# twip-mb2.net
KiCad netlist of a schematic drawn in EAGLE
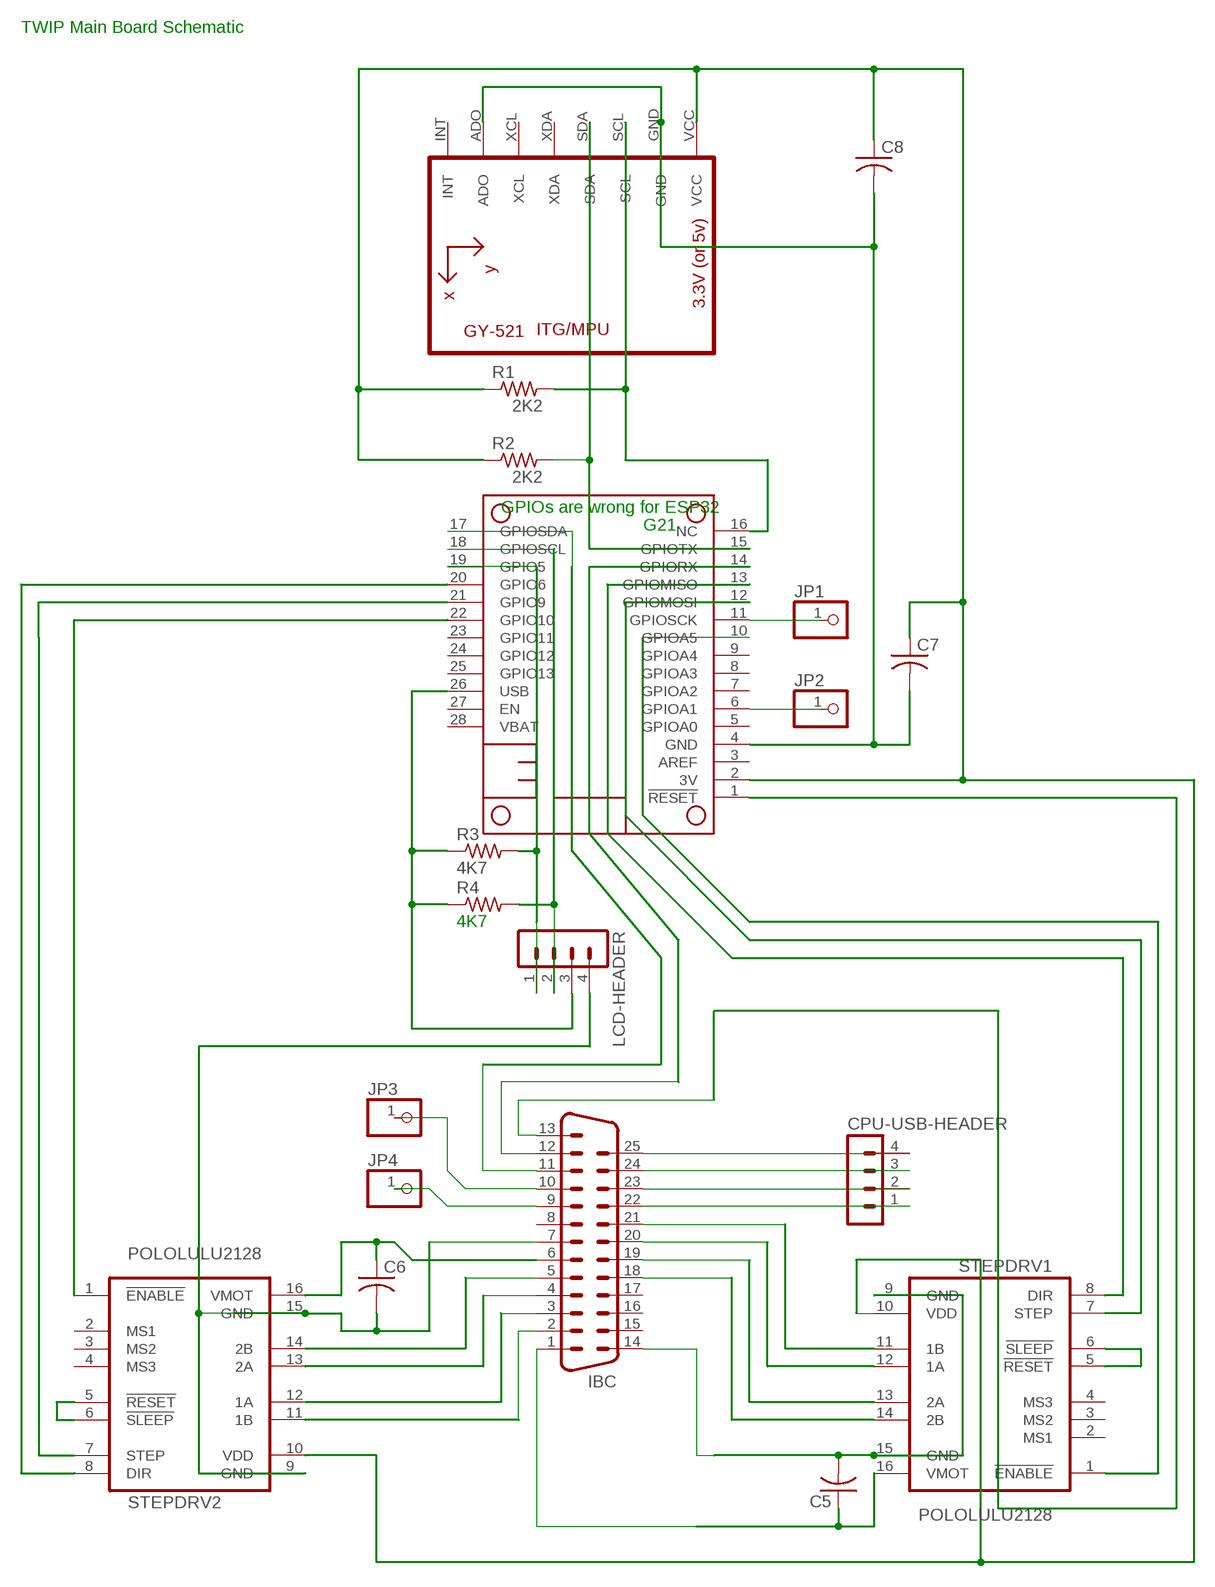
[diagram p0: schematic, sheet 1]

(export (version "E")
  (design (tool "Eeschema 10.0.6"))
  (components
    (comp (ref "C5")
      (value "C-US050-024X044")
      (footprint "eagle-import:C050-024X044")
      (libsource (lib "eagle-import") (part "C-US050-024X044"))
    )
    (comp (ref "C6")
      (value "C-US050-024X044")
      (footprint "eagle-import:C050-024X044")
      (libsource (lib "eagle-import") (part "C-US050-024X044"))
    )
    (comp (ref "C7")
      (value "C-US050-024X044")
      (footprint "eagle-import:C050-024X044")
      (libsource (lib "eagle-import") (part "C-US050-024X044"))
    )
    (comp (ref "C8")
      (value "C-US050-024X044")
      (footprint "eagle-import:C050-024X044")
      (libsource (lib "eagle-import") (part "C-US050-024X044"))
    )
    (comp (ref "CPU-USB-HEADER")
      (value "MA04-1")
      (footprint "eagle-import:MA04-1")
      (libsource (lib "eagle-import") (part "MA04-1"))
    )
    (comp (ref "IBC")
      (value "M25VP")
      (footprint "eagle-import:M25VP")
      (libsource (lib "eagle-import") (part "M25VP"))
    )
    (comp (ref "JP1")
      (value "PINHD-1X1")
      (footprint "eagle-import:1X01")
      (libsource (lib "eagle-import") (part "PINHD-1X1"))
    )
    (comp (ref "JP2")
      (value "PINHD-1X1")
      (footprint "eagle-import:1X01")
      (libsource (lib "eagle-import") (part "PINHD-1X1"))
    )
    (comp (ref "JP3")
      (value "PINHD-1X1")
      (footprint "eagle-import:1X01")
      (libsource (lib "eagle-import") (part "PINHD-1X1"))
    )
    (comp (ref "JP4")
      (value "PINHD-1X1")
      (footprint "eagle-import:1X01")
      (libsource (lib "eagle-import") (part "PINHD-1X1"))
    )
    (comp (ref "LCD-HEADER")
      (value "MA04-1")
      (footprint "eagle-import:MA04-1")
      (libsource (lib "eagle-import") (part "MA04-1"))
    )
    (comp (ref "MS2")
      (value "FEATHERWING_NOHOLES")
      (footprint "eagle-import:FEATHERWING_NOHOLES")
      (libsource (lib "eagle-import") (part "FEATHERWING_NOHOLES"))
    )
    (comp (ref "R1")
      (value "2K2")
      (footprint "eagle-import:0309_12")
      (libsource (lib "eagle-import") (part "R-US_0309/12"))
    )
    (comp (ref "R2")
      (value "2K2")
      (footprint "eagle-import:0309_12")
      (libsource (lib "eagle-import") (part "R-US_0309/12"))
    )
    (comp (ref "R3")
      (value "4K7")
      (footprint "eagle-import:0309_12")
      (libsource (lib "eagle-import") (part "R-US_0309/12"))
    )
    (comp (ref "R4")
      (value "4K7")
      (footprint "eagle-import:0309_12")
      (libsource (lib "eagle-import") (part "R-US_0309/12"))
    )
    (comp (ref "STEPDRV1")
      (value "POLOLULU2128")
      (footprint "eagle-import:POLOLULU2128")
      (libsource (lib "eagle-import") (part "POLOLULU2128"))
    )
    (comp (ref "STEPDRV2")
      (value "POLOLULU2128")
      (footprint "eagle-import:POLOLULU2128")
      (libsource (lib "eagle-import") (part "POLOLULU2128"))
    )
    (comp (ref "U1")
      (value "GY-521MPU6050")
      (footprint "eagle-import:GY-521")
      (libsource (lib "eagle-import") (part "GY-521MPU6050"))
    )
  )
  (nets
    (net (code "1") (name "/VBAT") (class "Default")
      (node (ref "MS2") (pin "28") (pinfunction "VBAT_28") (pintype "power_in"))
    )
    (net (code "2") (name "Net-(C5-Pad2)") (class "Default")
      (node (ref "C5") (pin "2") (pinfunction "2_2") (pintype "passive"))
      (node (ref "IBC") (pin "14") (pinfunction "14_14") (pintype "passive"))
      (node (ref "STEPDRV1") (pin "15") (pinfunction "GND_15") (pintype "power_in"))
      (node (ref "STEPDRV1") (pin "9") (pinfunction "GND_9") (pintype "power_in"))
    )
    (net (code "3") (name "Net-(C6-Pad2)") (class "Default")
      (node (ref "C6") (pin "2") (pinfunction "2_2") (pintype "passive"))
      (node (ref "IBC") (pin "7") (pinfunction "7_7") (pintype "passive"))
      (node (ref "LCD-HEADER") (pin "4") (pinfunction "4_4") (pintype "passive"))
      (node (ref "STEPDRV2") (pin "15") (pinfunction "GND_15") (pintype "power_in"))
      (node (ref "STEPDRV2") (pin "9") (pinfunction "GND_9") (pintype "power_in"))
    )
    (net (code "4") (name "Net-(CPU-USB-HEADER-Pad1)") (class "Default")
      (node (ref "CPU-USB-HEADER") (pin "1") (pinfunction "1_1") (pintype "passive"))
      (node (ref "IBC") (pin "22") (pinfunction "22_22") (pintype "passive"))
    )
    (net (code "5") (name "Net-(CPU-USB-HEADER-Pad2)") (class "Default")
      (node (ref "CPU-USB-HEADER") (pin "2") (pinfunction "2_2") (pintype "passive"))
      (node (ref "IBC") (pin "23") (pinfunction "23_23") (pintype "passive"))
    )
    (net (code "6") (name "Net-(CPU-USB-HEADER-Pad3)") (class "Default")
      (node (ref "CPU-USB-HEADER") (pin "3") (pinfunction "3_3") (pintype "passive"))
      (node (ref "IBC") (pin "24") (pinfunction "24_24") (pintype "passive"))
    )
    (net (code "7") (name "Net-(CPU-USB-HEADER-Pad4)") (class "Default")
      (node (ref "CPU-USB-HEADER") (pin "4") (pinfunction "4_4") (pintype "passive"))
      (node (ref "IBC") (pin "25") (pinfunction "25_25") (pintype "passive"))
    )
    (net (code "8") (name "Net-(IBC-Pad9)") (class "Default")
      (node (ref "IBC") (pin "9") (pinfunction "9_9") (pintype "passive"))
      (node (ref "JP4") (pin "1") (pinfunction "1_1") (pintype "passive"))
    )
    (net (code "9") (name "Net-(IBC-Pad10)") (class "Default")
      (node (ref "IBC") (pin "10") (pinfunction "10_10") (pintype "passive"))
      (node (ref "JP3") (pin "1") (pinfunction "1_1") (pintype "passive"))
    )
    (net (code "10") (name "Net-(MS2-3V)") (class "Default")
      (node (ref "C7") (pin "1") (pinfunction "1_1") (pintype "passive"))
      (node (ref "C8") (pin "1") (pinfunction "1_1") (pintype "passive"))
      (node (ref "MS2") (pin "2") (pinfunction "3V_2") (pintype "power_in"))
      (node (ref "R1") (pin "1") (pinfunction "1_1") (pintype "passive"))
      (node (ref "R2") (pin "1") (pinfunction "1_1") (pintype "passive"))
      (node (ref "STEPDRV1") (pin "10") (pinfunction "VDD_10") (pintype "power_in"))
      (node (ref "STEPDRV2") (pin "10") (pinfunction "VDD_10") (pintype "power_in"))
      (node (ref "U1") (pin "VCC") (pinfunction "VCC_VCC") (pintype "bidirectional"))
    )
    (net (code "11") (name "Net-(MS2-GND)") (class "Default")
      (node (ref "C7") (pin "2") (pinfunction "2_2") (pintype "passive"))
      (node (ref "C8") (pin "2") (pinfunction "2_2") (pintype "passive"))
      (node (ref "MS2") (pin "4") (pinfunction "GND_4") (pintype "power_in"))
      (node (ref "U1") (pin "ADO") (pinfunction "ADO_ADO") (pintype "bidirectional"))
      (node (ref "U1") (pin "GND") (pinfunction "GND_GND") (pintype "bidirectional"))
    )
    (net (code "12") (name "Net-(MS2-GPIO5)") (class "Default")
      (node (ref "LCD-HEADER") (pin "1") (pinfunction "1_1") (pintype "passive"))
      (node (ref "MS2") (pin "19") (pinfunction "GPIO5_19") (pintype "bidirectional"))
      (node (ref "R3") (pin "2") (pinfunction "2_2") (pintype "passive"))
    )
    (net (code "13") (name "Net-(MS2-GPIO6)") (class "Default")
      (node (ref "MS2") (pin "20") (pinfunction "GPIO6_20") (pintype "bidirectional"))
      (node (ref "STEPDRV2") (pin "8") (pinfunction "DIR_8") (pintype "input"))
    )
    (net (code "14") (name "Net-(MS2-GPIO9)") (class "Default")
      (node (ref "MS2") (pin "21") (pinfunction "GPIO9_21") (pintype "bidirectional"))
      (node (ref "STEPDRV2") (pin "7") (pinfunction "STEP_7") (pintype "input"))
    )
    (net (code "15") (name "Net-(MS2-GPIO10)") (class "Default")
      (node (ref "MS2") (pin "22") (pinfunction "GPIO10_22") (pintype "bidirectional"))
      (node (ref "STEPDRV2") (pin "1") (pinfunction "~{ENABLE}_1") (pintype "input"))
    )
    (net (code "16") (name "Net-(MS2-GPIOA1)") (class "Default")
      (node (ref "JP2") (pin "1") (pinfunction "1_1") (pintype "passive"))
      (node (ref "MS2") (pin "6") (pinfunction "GPIOA1_6") (pintype "bidirectional"))
    )
    (net (code "17") (name "Net-(MS2-GPIOA5)") (class "Default")
      (node (ref "MS2") (pin "10") (pinfunction "GPIOA5_10") (pintype "bidirectional"))
      (node (ref "STEPDRV1") (pin "1") (pinfunction "~{ENABLE}_1") (pintype "input"))
    )
    (net (code "18") (name "Net-(MS2-GPIOMISO)") (class "Default")
      (node (ref "MS2") (pin "13") (pinfunction "GPIOMISO_13") (pintype "bidirectional"))
      (node (ref "STEPDRV1") (pin "8") (pinfunction "DIR_8") (pintype "input"))
    )
    (net (code "19") (name "Net-(MS2-GPIOMOSI)") (class "Default")
      (node (ref "MS2") (pin "12") (pinfunction "GPIOMOSI_12") (pintype "bidirectional"))
      (node (ref "STEPDRV1") (pin "7") (pinfunction "STEP_7") (pintype "input"))
    )
    (net (code "20") (name "Net-(MS2-GPIORX)") (class "Default")
      (node (ref "IBC") (pin "12") (pinfunction "12_12") (pintype "passive"))
      (node (ref "MS2") (pin "14") (pinfunction "GPIORX_14") (pintype "bidirectional"))
    )
    (net (code "21") (name "Net-(MS2-GPIOSCK)") (class "Default")
      (node (ref "JP1") (pin "1") (pinfunction "1_1") (pintype "passive"))
      (node (ref "MS2") (pin "11") (pinfunction "GPIOSCK_11") (pintype "bidirectional"))
    )
    (net (code "22") (name "Net-(MS2-GPIOSCL)") (class "Default")
      (node (ref "LCD-HEADER") (pin "2") (pinfunction "2_2") (pintype "passive"))
      (node (ref "MS2") (pin "18") (pinfunction "GPIOSCL_18") (pintype "bidirectional"))
      (node (ref "R4") (pin "2") (pinfunction "2_2") (pintype "passive"))
    )
    (net (code "23") (name "Net-(MS2-GPIOSDA)") (class "Default")
      (node (ref "IBC") (pin "11") (pinfunction "11_11") (pintype "passive"))
      (node (ref "MS2") (pin "17") (pinfunction "GPIOSDA_17") (pintype "bidirectional"))
    )
    (net (code "24") (name "Net-(MS2-GPIOTX)") (class "Default")
      (node (ref "MS2") (pin "15") (pinfunction "GPIOTX_15") (pintype "bidirectional"))
      (node (ref "R2") (pin "2") (pinfunction "2_2") (pintype "passive"))
      (node (ref "U1") (pin "SDA") (pinfunction "SDA_SDA") (pintype "bidirectional"))
    )
    (net (code "25") (name "Net-(MS2-NC)") (class "Default")
      (node (ref "MS2") (pin "16") (pinfunction "NC_16") (pintype "passive"))
      (node (ref "R1") (pin "2") (pinfunction "2_2") (pintype "passive"))
      (node (ref "U1") (pin "SCL") (pinfunction "SCL_SCL") (pintype "bidirectional"))
    )
    (net (code "26") (name "Net-(MS2-USB)") (class "Default")
      (node (ref "LCD-HEADER") (pin "3") (pinfunction "3_3") (pintype "passive"))
      (node (ref "MS2") (pin "26") (pinfunction "USB_26") (pintype "power_in"))
      (node (ref "R3") (pin "1") (pinfunction "1_1") (pintype "passive"))
      (node (ref "R4") (pin "1") (pinfunction "1_1") (pintype "passive"))
    )
    (net (code "27") (name "Net-(MS2-~{RESET})") (class "Default")
      (node (ref "IBC") (pin "13") (pinfunction "13_13") (pintype "passive"))
      (node (ref "MS2") (pin "1") (pinfunction "~{RESET}_1") (pintype "input"))
    )
    (net (code "28") (name "Net-(STEPDRV1-1A)") (class "Default")
      (node (ref "IBC") (pin "20") (pinfunction "20_20") (pintype "passive"))
      (node (ref "STEPDRV1") (pin "12") (pinfunction "1A_12") (pintype "output"))
    )
    (net (code "29") (name "Net-(STEPDRV1-1B)") (class "Default")
      (node (ref "IBC") (pin "21") (pinfunction "21_21") (pintype "passive"))
      (node (ref "STEPDRV1") (pin "11") (pinfunction "1B_11") (pintype "output"))
    )
    (net (code "30") (name "Net-(STEPDRV1-2A)") (class "Default")
      (node (ref "IBC") (pin "19") (pinfunction "19_19") (pintype "passive"))
      (node (ref "STEPDRV1") (pin "13") (pinfunction "2A_13") (pintype "output"))
    )
    (net (code "31") (name "Net-(STEPDRV1-2B)") (class "Default")
      (node (ref "IBC") (pin "18") (pinfunction "18_18") (pintype "passive"))
      (node (ref "STEPDRV1") (pin "14") (pinfunction "2B_14") (pintype "output"))
    )
    (net (code "32") (name "Net-(STEPDRV1-VMOT)") (class "Default")
      (node (ref "C5") (pin "1") (pinfunction "1_1") (pintype "passive"))
      (node (ref "IBC") (pin "1") (pinfunction "1_1") (pintype "passive"))
      (node (ref "STEPDRV1") (pin "16") (pinfunction "VMOT_16") (pintype "power_in"))
    )
    (net (code "33") (name "Net-(STEPDRV1-~{RESET})") (class "Default")
      (node (ref "STEPDRV1") (pin "5") (pinfunction "~{RESET}_5") (pintype "input"))
      (node (ref "STEPDRV1") (pin "6") (pinfunction "~{SLEEP}_6") (pintype "input"))
    )
    (net (code "34") (name "Net-(STEPDRV2-1A)") (class "Default")
      (node (ref "IBC") (pin "3") (pinfunction "3_3") (pintype "passive"))
      (node (ref "STEPDRV2") (pin "12") (pinfunction "1A_12") (pintype "output"))
    )
    (net (code "35") (name "Net-(STEPDRV2-1B)") (class "Default")
      (node (ref "IBC") (pin "2") (pinfunction "2_2") (pintype "passive"))
      (node (ref "STEPDRV2") (pin "11") (pinfunction "1B_11") (pintype "output"))
    )
    (net (code "36") (name "Net-(STEPDRV2-2A)") (class "Default")
      (node (ref "IBC") (pin "4") (pinfunction "4_4") (pintype "passive"))
      (node (ref "STEPDRV2") (pin "13") (pinfunction "2A_13") (pintype "output"))
    )
    (net (code "37") (name "Net-(STEPDRV2-2B)") (class "Default")
      (node (ref "IBC") (pin "5") (pinfunction "5_5") (pintype "passive"))
      (node (ref "STEPDRV2") (pin "14") (pinfunction "2B_14") (pintype "output"))
    )
    (net (code "38") (name "Net-(STEPDRV2-VMOT)") (class "Default")
      (node (ref "C6") (pin "1") (pinfunction "1_1") (pintype "passive"))
      (node (ref "IBC") (pin "6") (pinfunction "6_6") (pintype "passive"))
      (node (ref "STEPDRV2") (pin "16") (pinfunction "VMOT_16") (pintype "power_in"))
    )
    (net (code "39") (name "Net-(STEPDRV2-~{RESET})") (class "Default")
      (node (ref "STEPDRV2") (pin "5") (pinfunction "~{RESET}_5") (pintype "input"))
      (node (ref "STEPDRV2") (pin "6") (pinfunction "~{SLEEP}_6") (pintype "input"))
    )
    (net (code "40") (name "unconnected-(IBC-Pad8)") (class "Default")
      (node (ref "IBC") (pin "8") (pinfunction "8_8") (pintype "passive"))
    )
    (net (code "41") (name "unconnected-(IBC-Pad15)") (class "Default")
      (node (ref "IBC") (pin "15") (pinfunction "15_15") (pintype "passive"))
    )
    (net (code "42") (name "unconnected-(IBC-Pad16)") (class "Default")
      (node (ref "IBC") (pin "16") (pinfunction "16_16") (pintype "passive"))
    )
    (net (code "43") (name "unconnected-(IBC-Pad17)") (class "Default")
      (node (ref "IBC") (pin "17") (pinfunction "17_17") (pintype "passive"))
    )
    (net (code "44") (name "unconnected-(MS2-AREF-Pad3)") (class "Default")
      (node (ref "MS2") (pin "3") (pinfunction "AREF_3") (pintype "passive"))
    )
    (net (code "45") (name "unconnected-(MS2-EN-Pad27)") (class "Default")
      (node (ref "MS2") (pin "27") (pinfunction "EN_27") (pintype "passive"))
    )
    (net (code "46") (name "unconnected-(MS2-GPIO11-Pad23)") (class "Default")
      (node (ref "MS2") (pin "23") (pinfunction "GPIO11_23") (pintype "bidirectional"))
    )
    (net (code "47") (name "unconnected-(MS2-GPIO12-Pad24)") (class "Default")
      (node (ref "MS2") (pin "24") (pinfunction "GPIO12_24") (pintype "bidirectional"))
    )
    (net (code "48") (name "unconnected-(MS2-GPIO13-Pad25)") (class "Default")
      (node (ref "MS2") (pin "25") (pinfunction "GPIO13_25") (pintype "bidirectional"))
    )
    (net (code "49") (name "unconnected-(MS2-GPIOA0-Pad5)") (class "Default")
      (node (ref "MS2") (pin "5") (pinfunction "GPIOA0_5") (pintype "bidirectional"))
    )
    (net (code "50") (name "unconnected-(MS2-GPIOA2-Pad7)") (class "Default")
      (node (ref "MS2") (pin "7") (pinfunction "GPIOA2_7") (pintype "bidirectional"))
    )
    (net (code "51") (name "unconnected-(MS2-GPIOA3-Pad8)") (class "Default")
      (node (ref "MS2") (pin "8") (pinfunction "GPIOA3_8") (pintype "bidirectional"))
    )
    (net (code "52") (name "unconnected-(MS2-GPIOA4-Pad9)") (class "Default")
      (node (ref "MS2") (pin "9") (pinfunction "GPIOA4_9") (pintype "bidirectional"))
    )
    (net (code "53") (name "unconnected-(STEPDRV1-MS1-Pad2)") (class "Default")
      (node (ref "STEPDRV1") (pin "2") (pinfunction "MS1_2") (pintype "input"))
    )
    (net (code "54") (name "unconnected-(STEPDRV1-MS2-Pad3)") (class "Default")
      (node (ref "STEPDRV1") (pin "3") (pinfunction "MS2_3") (pintype "input"))
    )
    (net (code "55") (name "unconnected-(STEPDRV1-MS3-Pad4)") (class "Default")
      (node (ref "STEPDRV1") (pin "4") (pinfunction "MS3_4") (pintype "input"))
    )
    (net (code "56") (name "unconnected-(STEPDRV2-MS1-Pad2)") (class "Default")
      (node (ref "STEPDRV2") (pin "2") (pinfunction "MS1_2") (pintype "input"))
    )
    (net (code "57") (name "unconnected-(STEPDRV2-MS2-Pad3)") (class "Default")
      (node (ref "STEPDRV2") (pin "3") (pinfunction "MS2_3") (pintype "input"))
    )
    (net (code "58") (name "unconnected-(STEPDRV2-MS3-Pad4)") (class "Default")
      (node (ref "STEPDRV2") (pin "4") (pinfunction "MS3_4") (pintype "input"))
    )
    (net (code "59") (name "unconnected-(U1-PadINT)") (class "Default")
      (node (ref "U1") (pin "INT") (pinfunction "INT_INT") (pintype "bidirectional"))
    )
    (net (code "60") (name "unconnected-(U1-PadXCL)") (class "Default")
      (node (ref "U1") (pin "XCL") (pinfunction "XCL_XCL") (pintype "bidirectional"))
    )
    (net (code "61") (name "unconnected-(U1-PadXDA)") (class "Default")
      (node (ref "U1") (pin "XDA") (pinfunction "XDA_XDA") (pintype "bidirectional"))
    )
  )
)
